# POWER_CON.net
KiCad netlist of a schematic drawn in Altium Designer
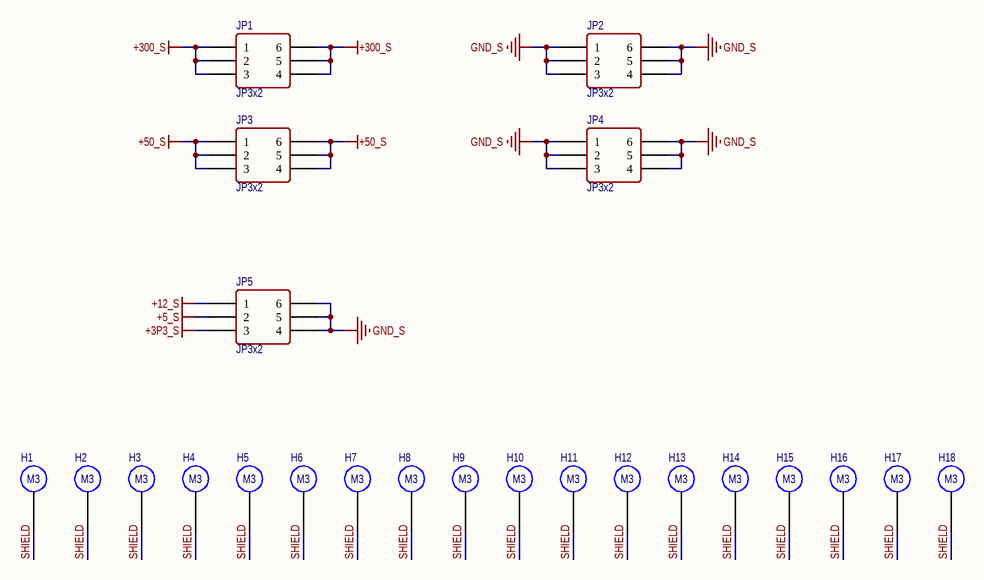
[diagram p0: POWER_CON.SchDoc]

(export (version "E")
  (design (tool "Eeschema 10.0.6"))
  (components
    (comp (ref "H1") (value "M3") (footprint "M3") (libsource (lib "Library") (part "M3")))
    (comp (ref "H2") (value "M3") (footprint "M3") (libsource (lib "Library") (part "M3")))
    (comp (ref "H3") (value "M3") (footprint "M3") (libsource (lib "Library") (part "M3")))
    (comp (ref "H4") (value "M3") (footprint "M3") (libsource (lib "Library") (part "M3")))
    (comp (ref "H5") (value "M3") (footprint "M3") (libsource (lib "Library") (part "M3")))
    (comp (ref "H6") (value "M3") (footprint "M3") (libsource (lib "Library") (part "M3")))
    (comp (ref "H7") (value "M3") (footprint "M3") (libsource (lib "Library") (part "M3")))
    (comp (ref "H8") (value "M3") (footprint "M3") (libsource (lib "Library") (part "M3")))
    (comp (ref "H9") (value "M3") (footprint "M3") (libsource (lib "Library") (part "M3")))
    (comp (ref "H10") (value "M3") (footprint "M3") (libsource (lib "Library") (part "M3")))
    (comp (ref "H11") (value "M3") (footprint "M3") (libsource (lib "Library") (part "M3")))
    (comp (ref "H12") (value "M3") (footprint "M3") (libsource (lib "Library") (part "M3")))
    (comp (ref "H13") (value "M3") (footprint "M3") (libsource (lib "Library") (part "M3")))
    (comp (ref "H14") (value "M3") (footprint "M3") (libsource (lib "Library") (part "M3")))
    (comp (ref "H15") (value "M3") (footprint "M3") (libsource (lib "Library") (part "M3")))
    (comp (ref "H16") (value "M3") (footprint "M3") (libsource (lib "Library") (part "M3")))
    (comp (ref "H17") (value "M3") (footprint "M3") (libsource (lib "Library") (part "M3")))
    (comp (ref "H18") (value "M3") (footprint "M3") (libsource (lib "Library") (part "M3")))
    (comp (ref "JP1")
      (value "JP3x2")
      (footprint "JP3-D2T")
      (description "5-534206-3")
      (fields
        (field (name "MANUFACTURER") "Würth Elektronik eiSos GmbH")
        (field (name "PARTNO") "61300621821")
        (field (name "CREATED BY") "Karrer Zheng")
      )
      (libsource (lib "Library") (part "JP3x2"))
    )
    (comp (ref "JP2")
      (value "JP3x2")
      (footprint "JP3-D2T")
      (description "5-534206-3")
      (fields
        (field (name "MANUFACTURER") "Würth Elektronik eiSos GmbH")
        (field (name "PARTNO") "61300621821")
        (field (name "CREATED BY") "Karrer Zheng")
      )
      (libsource (lib "Library") (part "JP3x2"))
    )
    (comp (ref "JP3")
      (value "JP3x2")
      (footprint "JP3-D2T")
      (description "5-534206-3")
      (fields
        (field (name "MANUFACTURER") "Würth Elektronik eiSos GmbH")
        (field (name "PARTNO") "61300621821")
        (field (name "CREATED BY") "Karrer Zheng")
      )
      (libsource (lib "Library") (part "JP3x2"))
    )
    (comp (ref "JP4")
      (value "JP3x2")
      (footprint "JP3-D2T")
      (description "5-534206-3")
      (fields
        (field (name "MANUFACTURER") "Würth Elektronik eiSos GmbH")
        (field (name "PARTNO") "61300621821")
        (field (name "CREATED BY") "Karrer Zheng")
      )
      (libsource (lib "Library") (part "JP3x2"))
    )
    (comp (ref "JP5")
      (value "JP3x2")
      (footprint "JP3-D2T")
      (description "5-534206-3")
      (fields
        (field (name "MANUFACTURER") "Würth Elektronik eiSos GmbH")
        (field (name "PARTNO") "61300621821")
        (field (name "CREATED BY") "Karrer Zheng")
      )
      (libsource (lib "Library") (part "JP3x2"))
    )
  )
  (nets
    (net (code "1") (name "+3P3_S") (class "Default")
      (node (ref "JP5") (pin "3") (pinfunction "3_3") (pintype "passive"))
    )
    (net (code "2") (name "+5_S") (class "Default")
      (node (ref "JP5") (pin "2") (pinfunction "2_2") (pintype "passive"))
    )
    (net (code "3") (name "+12_S") (class "Default")
      (node (ref "JP5") (pin "1") (pinfunction "1_1") (pintype "passive"))
    )
    (net (code "4") (name "+50_S") (class "Default")
      (node (ref "JP3") (pin "1") (pinfunction "1_1") (pintype "passive"))
      (node (ref "JP3") (pin "2") (pinfunction "2_2") (pintype "passive"))
      (node (ref "JP3") (pin "3") (pinfunction "3_3") (pintype "passive"))
      (node (ref "JP3") (pin "4") (pinfunction "4_4") (pintype "passive"))
      (node (ref "JP3") (pin "5") (pinfunction "5_5") (pintype "passive"))
      (node (ref "JP3") (pin "6") (pinfunction "6_6") (pintype "passive"))
    )
    (net (code "5") (name "+300_S") (class "Default")
      (node (ref "JP1") (pin "1") (pinfunction "1_1") (pintype "passive"))
      (node (ref "JP1") (pin "2") (pinfunction "2_2") (pintype "passive"))
      (node (ref "JP1") (pin "3") (pinfunction "3_3") (pintype "passive"))
      (node (ref "JP1") (pin "4") (pinfunction "4_4") (pintype "passive"))
      (node (ref "JP1") (pin "5") (pinfunction "5_5") (pintype "passive"))
      (node (ref "JP1") (pin "6") (pinfunction "6_6") (pintype "passive"))
    )
    (net (code "6") (name "/SHIELD") (class "Default")
      (node (ref "H1") (pin "1") (pinfunction "76_1") (pintype "passive"))
      (node (ref "H10") (pin "1") (pinfunction "76_1") (pintype "passive"))
      (node (ref "H11") (pin "1") (pinfunction "76_1") (pintype "passive"))
      (node (ref "H12") (pin "1") (pinfunction "76_1") (pintype "passive"))
      (node (ref "H13") (pin "1") (pinfunction "76_1") (pintype "passive"))
      (node (ref "H14") (pin "1") (pinfunction "76_1") (pintype "passive"))
      (node (ref "H15") (pin "1") (pinfunction "76_1") (pintype "passive"))
      (node (ref "H16") (pin "1") (pinfunction "76_1") (pintype "passive"))
      (node (ref "H17") (pin "1") (pinfunction "76_1") (pintype "passive"))
      (node (ref "H18") (pin "1") (pinfunction "76_1") (pintype "passive"))
      (node (ref "H2") (pin "1") (pinfunction "76_1") (pintype "passive"))
      (node (ref "H3") (pin "1") (pinfunction "76_1") (pintype "passive"))
      (node (ref "H4") (pin "1") (pinfunction "76_1") (pintype "passive"))
      (node (ref "H5") (pin "1") (pinfunction "76_1") (pintype "passive"))
      (node (ref "H6") (pin "1") (pinfunction "76_1") (pintype "passive"))
      (node (ref "H7") (pin "1") (pinfunction "76_1") (pintype "passive"))
      (node (ref "H8") (pin "1") (pinfunction "76_1") (pintype "passive"))
      (node (ref "H9") (pin "1") (pinfunction "76_1") (pintype "passive"))
    )
    (net (code "7") (name "GND_S") (class "Default")
      (node (ref "JP2") (pin "1") (pinfunction "1_1") (pintype "passive"))
      (node (ref "JP2") (pin "2") (pinfunction "2_2") (pintype "passive"))
      (node (ref "JP2") (pin "3") (pinfunction "3_3") (pintype "passive"))
      (node (ref "JP2") (pin "4") (pinfunction "4_4") (pintype "passive"))
      (node (ref "JP2") (pin "5") (pinfunction "5_5") (pintype "passive"))
      (node (ref "JP2") (pin "6") (pinfunction "6_6") (pintype "passive"))
      (node (ref "JP4") (pin "1") (pinfunction "1_1") (pintype "passive"))
      (node (ref "JP4") (pin "2") (pinfunction "2_2") (pintype "passive"))
      (node (ref "JP4") (pin "3") (pinfunction "3_3") (pintype "passive"))
      (node (ref "JP4") (pin "4") (pinfunction "4_4") (pintype "passive"))
      (node (ref "JP4") (pin "5") (pinfunction "5_5") (pintype "passive"))
      (node (ref "JP4") (pin "6") (pinfunction "6_6") (pintype "passive"))
      (node (ref "JP5") (pin "4") (pinfunction "4_4") (pintype "passive"))
      (node (ref "JP5") (pin "5") (pinfunction "5_5") (pintype "passive"))
      (node (ref "JP5") (pin "6") (pinfunction "6_6") (pintype "passive"))
    )
  )
)
